# Button_Board.net
KiCad netlist of a schematic drawn in Altium Designer
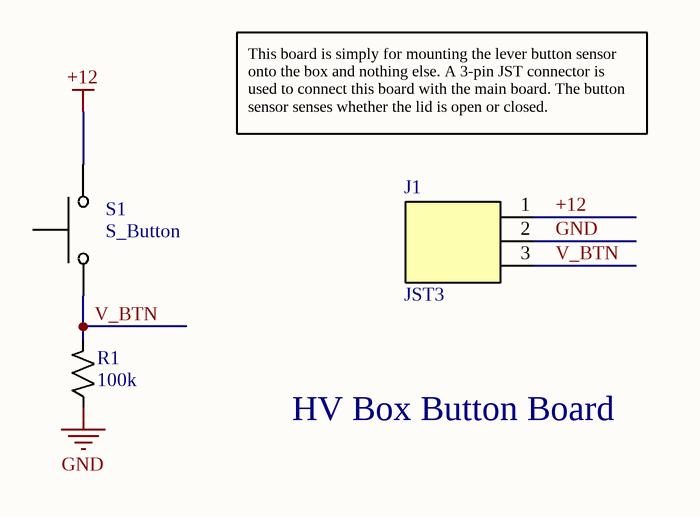
[diagram p0: Button_Board.SchDoc]

(export (version "E")
  (design (tool "Eeschema 10.0.6"))
  (components
    (comp (ref "J1")
      (value "JST3")
      (footprint "JST_3")
      (description "Jack JST 3-pin")
      (libsource (lib "HV_Box_IntLib") (part "J_JST_3"))
    )
    (comp (ref "R1")
      (value "100k")
      (footprint "0603_RES")
      (description "Resistor 100 kOhm 0603 1%")
      (libsource (lib "Load_Bank_New_IntLib") (part "R_100kOhm_0603_1%"))
    )
    (comp (ref "S1")
      (value "S_Button")
      (footprint "BUTTON")
      (description "Switch Button")
      (libsource (lib "HV_Box_IntLib") (part "S_Button"))
    )
  )
  (nets
    (net (code "1") (name "+12") (class "Default")
      (node (ref "J1") (pin "1") (pinfunction "Sig1_1") (pintype "passive"))
      (node (ref "S1") (pin "1") (pinfunction "1_1") (pintype "passive"))
    )
    (net (code "2") (name "/V_BTN") (class "Default")
      (node (ref "J1") (pin "3") (pinfunction "NC_3") (pintype "passive"))
      (node (ref "R1") (pin "2") (pintype "passive"))
      (node (ref "S1") (pin "2") (pinfunction "2_2") (pintype "passive"))
    )
    (net (code "3") (name "GND") (class "Default")
      (node (ref "J1") (pin "2") (pinfunction "Sig2_2") (pintype "passive"))
      (node (ref "R1") (pin "1") (pintype "passive"))
    )
  )
)
